# SixPotatoeV7.net
KiCad netlist of a schematic drawn in EAGLE
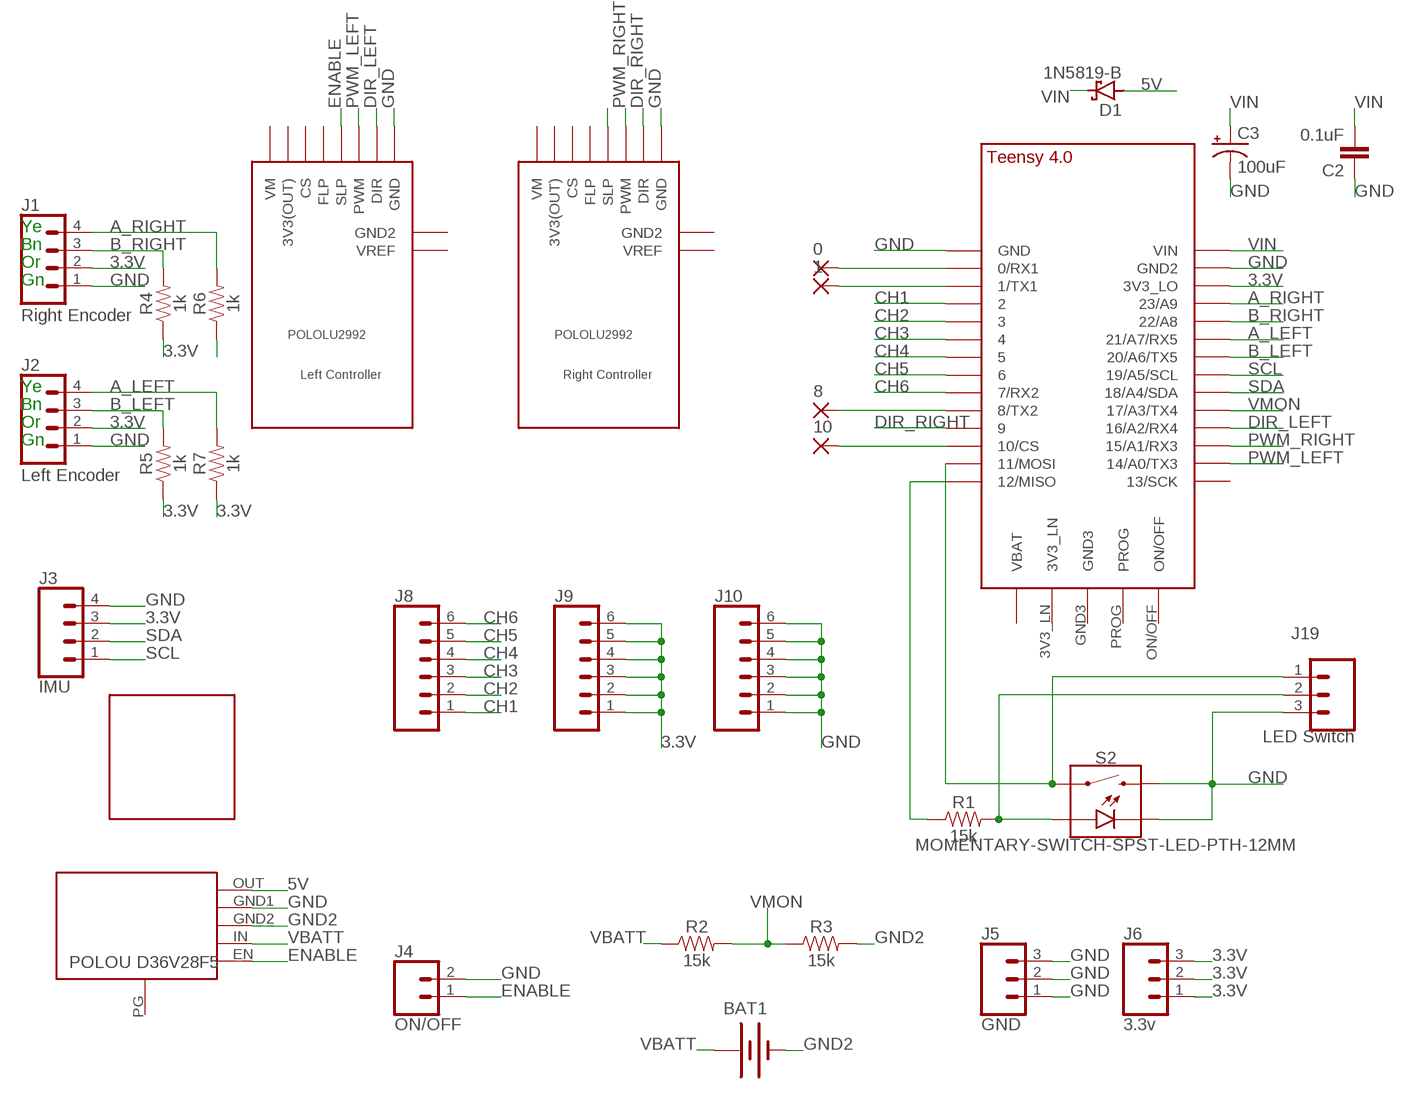
[diagram p0: schematic, sheet 1]

(export (version "E")
  (design (tool "Eeschema 10.0.6"))
  (components
    (comp (ref "0")
      (value "2,15/1,0")
      (footprint "eagle-import:2,15_1,0")
      (libsource (lib "eagle-import") (part "2,15/1,0"))
    )
    (comp (ref "1")
      (value "2,15/1,0")
      (footprint "eagle-import:2,15_1,0")
      (libsource (lib "eagle-import") (part "2,15/1,0"))
    )
    (comp (ref "8")
      (value "2,15/1,0")
      (footprint "eagle-import:2,15_1,0")
      (libsource (lib "eagle-import") (part "2,15/1,0"))
    )
    (comp (ref "10")
      (value "2,15/1,0")
      (footprint "eagle-import:2,15_1,0")
      (libsource (lib "eagle-import") (part "2,15/1,0"))
    )
    (comp (ref "BAT1")
      (value "XT60_MALE")
      (footprint "eagle-import:XT60")
      (libsource (lib "eagle-import") (part "XT60_MALE"))
    )
    (comp (ref "C2")
      (value "0.1uF")
      (footprint "eagle-import:CAP-PTH-SMALL-KIT")
      (libsource (lib "eagle-import") (part "0.1UF-KIT-EZ-50V-20%"))
    )
    (comp (ref "C3")
      (value "100uF")
      (footprint "eagle-import:CPOL-RADIAL-2.5MM-6.5MM")
      (libsource (lib "eagle-import") (part "100UF-POLAR-RADIAL-2.5MM-25V-20%"))
    )
    (comp (ref "D1")
      (value "1N5819-B")
      (footprint "eagle-import:DO41-7.6")
      (libsource (lib "eagle-import") (part "1N5819-B"))
    )
    (comp (ref "J1")
      (value "CONN_04")
      (footprint "eagle-import:1X04")
      (fields (field (name "ID") "Right Encoder"))
      (libsource (lib "eagle-import") (part "CONN_04"))
    )
    (comp (ref "J2")
      (value "CONN_04")
      (footprint "eagle-import:1X04")
      (fields (field (name "ID") "Left Encoder"))
      (libsource (lib "eagle-import") (part "CONN_04"))
    )
    (comp (ref "J3")
      (value "IMU")
      (footprint "eagle-import:1X04")
      (libsource (lib "eagle-import") (part "CONN_04"))
    )
    (comp (ref "J4")
      (value "ON/OFF")
      (footprint "eagle-import:1X02")
      (libsource (lib "eagle-import") (part "CONN_02"))
    )
    (comp (ref "J5")
      (value "GND")
      (footprint "eagle-import:1X03")
      (libsource (lib "eagle-import") (part "CONN_03"))
    )
    (comp (ref "J6")
      (value "3.3v")
      (footprint "eagle-import:1X03")
      (libsource (lib "eagle-import") (part "CONN_03"))
    )
    (comp (ref "J8")
      (value "CONN_06NO_SILK_FEMALE_PTH")
      (footprint "eagle-import:1X06_NO_SILK")
      (libsource (lib "eagle-import") (part "CONN_06NO_SILK_FEMALE_PTH"))
    )
    (comp (ref "J9")
      (value "CONN_06NO_SILK_FEMALE_PTH")
      (footprint "eagle-import:1X06_NO_SILK")
      (libsource (lib "eagle-import") (part "CONN_06NO_SILK_FEMALE_PTH"))
    )
    (comp (ref "J10")
      (value "CONN_06NO_SILK_FEMALE_PTH")
      (footprint "eagle-import:1X06_NO_SILK")
      (libsource (lib "eagle-import") (part "CONN_06NO_SILK_FEMALE_PTH"))
    )
    (comp (ref "J19")
      (value "CONN_03")
      (footprint "eagle-import:1X03")
      (fields (field (name "ID") "LED Switch"))
      (libsource (lib "eagle-import") (part "CONN_03"))
    )
    (comp (ref "R1")
      (value "15k")
      (footprint "eagle-import:AXIAL-0.3")
      (libsource (lib "eagle-import") (part "15KOHM-HORIZ-1/4W-5%"))
    )
    (comp (ref "R2")
      (value "15k")
      (footprint "eagle-import:AXIAL-0.3")
      (libsource (lib "eagle-import") (part "15KOHM-HORIZ-1/4W-5%"))
    )
    (comp (ref "R3")
      (value "15k")
      (footprint "eagle-import:AXIAL-0.3")
      (libsource (lib "eagle-import") (part "15KOHM-HORIZ-1/4W-5%"))
    )
    (comp (ref "R4")
      (value "1k")
      (footprint "eagle-import:AXIAL-0.3")
      (libsource (lib "eagle-import") (part "1KOHM-HORIZ-1/4W-1%"))
    )
    (comp (ref "R5")
      (value "1k")
      (footprint "eagle-import:AXIAL-0.3")
      (libsource (lib "eagle-import") (part "1KOHM-HORIZ-1/4W-1%"))
    )
    (comp (ref "R6")
      (value "1k")
      (footprint "eagle-import:AXIAL-0.3")
      (libsource (lib "eagle-import") (part "1KOHM-HORIZ-1/4W-1%"))
    )
    (comp (ref "R7")
      (value "1k")
      (footprint "eagle-import:AXIAL-0.3")
      (libsource (lib "eagle-import") (part "1KOHM-HORIZ-1/4W-1%"))
    )
    (comp (ref "S2")
      (value "MOMENTARY-SWITCH-SPST-LED-PTH-12MM")
      (footprint "eagle-import:TACTILE_SWITCH_LED_PTH_12MM")
      (libsource (lib "eagle-import") (part "MOMENTARY-SWITCH-SPST-LED-PTH-12MM"))
    )
    (comp (ref "U$1")
      (value "TEENSY_4.0")
      (footprint "eagle-import:TEENSY_4.0")
      (libsource (lib "eagle-import") (part "TEENSY_4.0"))
    )
    (comp (ref "U$2")
      (value "Left Controller")
      (footprint "eagle-import:POLOLU2992_2")
      (libsource (lib "eagle-import") (part "POLOLU2992_2"))
    )
    (comp (ref "U$3")
      (value "Right Controller")
      (footprint "eagle-import:POLOLU2992_2")
      (libsource (lib "eagle-import") (part "POLOLU2992_2"))
    )
    (comp (ref "U$4")
      (value "POLOU3782")
      (footprint "eagle-import:POLOU3782")
      (libsource (lib "eagle-import") (part "POLOU3782"))
    )
    (comp (ref "U$5")
      (value "SEN15335_NO_PTH")
      (footprint "eagle-import:SEN15335_NO_PTH")
      (libsource (lib "eagle-import") (part "SEN15335_NO_PTH"))
    )
  )
  (nets
    (net (code "1") (name "/3.3V") (class "Default")
      (node (ref "J1") (pin "2") (pinfunction "2_2") (pintype "passive"))
      (node (ref "J2") (pin "2") (pinfunction "2_2") (pintype "passive"))
      (node (ref "J3") (pin "3") (pinfunction "3_3") (pintype "passive"))
      (node (ref "J6") (pin "1") (pinfunction "1_1") (pintype "passive"))
      (node (ref "J6") (pin "2") (pinfunction "2_2") (pintype "passive"))
      (node (ref "J6") (pin "3") (pinfunction "3_3") (pintype "passive"))
      (node (ref "J9") (pin "1") (pinfunction "1_1") (pintype "passive"))
      (node (ref "J9") (pin "2") (pinfunction "2_2") (pintype "passive"))
      (node (ref "J9") (pin "3") (pinfunction "3_3") (pintype "passive"))
      (node (ref "J9") (pin "4") (pinfunction "4_4") (pintype "passive"))
      (node (ref "J9") (pin "5") (pinfunction "5_5") (pintype "passive"))
      (node (ref "J9") (pin "6") (pinfunction "6_6") (pintype "passive"))
      (node (ref "R4") (pin "P$1") (pinfunction "1_P$1") (pintype "passive"))
      (node (ref "R5") (pin "P$1") (pinfunction "1_P$1") (pintype "passive"))
      (node (ref "R6") (pin "P$1") (pinfunction "1_P$1") (pintype "passive"))
      (node (ref "R7") (pin "P$1") (pinfunction "1_P$1") (pintype "passive"))
      (node (ref "U$1") (pin "3V3_LO") (pinfunction "3V3_LO_3V3_LO") (pintype "bidirectional"))
    )
    (net (code "2") (name "/5V") (class "Default")
      (node (ref "D1") (pin "A") (pinfunction "A_A") (pintype "passive"))
      (node (ref "U$4") (pin "OUT") (pinfunction "OUT_OUT") (pintype "bidirectional"))
    )
    (net (code "3") (name "/A_LEFT") (class "Default")
      (node (ref "J2") (pin "4") (pinfunction "4_4") (pintype "passive"))
      (node (ref "R7") (pin "P$2") (pinfunction "2_P$2") (pintype "passive"))
      (node (ref "U$1") (pin "21/A7") (pinfunction "21/A7/RX5_21/A7") (pintype "bidirectional"))
    )
    (net (code "4") (name "/A_RIGHT") (class "Default")
      (node (ref "J1") (pin "4") (pinfunction "4_4") (pintype "passive"))
      (node (ref "R6") (pin "P$2") (pinfunction "2_P$2") (pintype "passive"))
      (node (ref "U$1") (pin "23/A9") (pinfunction "23/A9_23/A9") (pintype "bidirectional"))
    )
    (net (code "5") (name "/B_LEFT") (class "Default")
      (node (ref "J2") (pin "3") (pinfunction "3_3") (pintype "passive"))
      (node (ref "R5") (pin "P$2") (pinfunction "2_P$2") (pintype "passive"))
      (node (ref "U$1") (pin "20/A6") (pinfunction "20/A6/TX5_20/A6") (pintype "bidirectional"))
    )
    (net (code "6") (name "/B_RIGHT") (class "Default")
      (node (ref "J1") (pin "3") (pinfunction "3_3") (pintype "passive"))
      (node (ref "R4") (pin "P$2") (pinfunction "2_P$2") (pintype "passive"))
      (node (ref "U$1") (pin "22/A8") (pinfunction "22/A8_22/A8") (pintype "bidirectional"))
    )
    (net (code "7") (name "/CH1") (class "Default")
      (node (ref "J8") (pin "1") (pinfunction "1_1") (pintype "passive"))
      (node (ref "U$1") (pin "2") (pinfunction "2_2") (pintype "bidirectional"))
    )
    (net (code "8") (name "/CH2") (class "Default")
      (node (ref "J8") (pin "2") (pinfunction "2_2") (pintype "passive"))
      (node (ref "U$1") (pin "3/CANTX") (pinfunction "3_3/CANTX") (pintype "bidirectional"))
    )
    (net (code "9") (name "/CH3") (class "Default")
      (node (ref "J8") (pin "3") (pinfunction "3_3") (pintype "passive"))
      (node (ref "U$1") (pin "4/CANRX") (pinfunction "4_4/CANRX") (pintype "bidirectional"))
    )
    (net (code "10") (name "/CH4") (class "Default")
      (node (ref "J8") (pin "4") (pinfunction "4_4") (pintype "passive"))
      (node (ref "U$1") (pin "5") (pinfunction "5_5") (pintype "bidirectional"))
    )
    (net (code "11") (name "/CH5") (class "Default")
      (node (ref "J8") (pin "5") (pinfunction "5_5") (pintype "passive"))
      (node (ref "U$1") (pin "6") (pinfunction "6_6") (pintype "bidirectional"))
    )
    (net (code "12") (name "/CH6") (class "Default")
      (node (ref "J8") (pin "6") (pinfunction "6_6") (pintype "passive"))
      (node (ref "U$1") (pin "7") (pinfunction "7/RX2_7") (pintype "bidirectional"))
    )
    (net (code "13") (name "/DIR_LEFT") (class "Default")
      (node (ref "U$1") (pin "16/A2") (pinfunction "16/A2/RX4_16/A2") (pintype "bidirectional"))
      (node (ref "U$2") (pin "DIR") (pinfunction "DIR_DIR") (pintype "bidirectional"))
    )
    (net (code "14") (name "/DIR_RIGHT") (class "Default")
      (node (ref "U$1") (pin "9/CS") (pinfunction "9_9/CS") (pintype "bidirectional"))
      (node (ref "U$3") (pin "DIR") (pinfunction "DIR_DIR") (pintype "bidirectional"))
    )
    (net (code "15") (name "/ENABLE") (class "Default")
      (node (ref "J4") (pin "1") (pinfunction "1_1") (pintype "passive"))
      (node (ref "U$2") (pin "SLP") (pinfunction "SLP_SLP") (pintype "bidirectional"))
      (node (ref "U$3") (pin "SLP") (pinfunction "SLP_SLP") (pintype "bidirectional"))
      (node (ref "U$4") (pin "EN") (pinfunction "EN_EN") (pintype "bidirectional"))
    )
    (net (code "16") (name "/GND") (class "Default")
      (node (ref "C2") (pin "1") (pinfunction "1_1") (pintype "passive"))
      (node (ref "C3") (pin "2") (pinfunction "-_2") (pintype "passive"))
      (node (ref "J1") (pin "1") (pinfunction "1_1") (pintype "passive"))
      (node (ref "J10") (pin "1") (pinfunction "1_1") (pintype "passive"))
      (node (ref "J10") (pin "2") (pinfunction "2_2") (pintype "passive"))
      (node (ref "J10") (pin "3") (pinfunction "3_3") (pintype "passive"))
      (node (ref "J10") (pin "4") (pinfunction "4_4") (pintype "passive"))
      (node (ref "J10") (pin "5") (pinfunction "5_5") (pintype "passive"))
      (node (ref "J10") (pin "6") (pinfunction "6_6") (pintype "passive"))
      (node (ref "J19") (pin "3") (pinfunction "3_3") (pintype "passive"))
      (node (ref "J2") (pin "1") (pinfunction "1_1") (pintype "passive"))
      (node (ref "J3") (pin "4") (pinfunction "4_4") (pintype "passive"))
      (node (ref "J4") (pin "2") (pinfunction "2_2") (pintype "passive"))
      (node (ref "J5") (pin "1") (pinfunction "1_1") (pintype "passive"))
      (node (ref "J5") (pin "2") (pinfunction "2_2") (pintype "passive"))
      (node (ref "J5") (pin "3") (pinfunction "3_3") (pintype "passive"))
      (node (ref "S2") (pin "2") (pinfunction "2_2") (pintype "passive"))
      (node (ref "S2") (pin "C") (pinfunction "C_C") (pintype "passive"))
      (node (ref "U$1") (pin "GND") (pinfunction "GND_GND") (pintype "bidirectional"))
      (node (ref "U$1") (pin "GND2") (pinfunction "GND2_GND2") (pintype "bidirectional"))
      (node (ref "U$2") (pin "GND") (pinfunction "GND_GND") (pintype "bidirectional"))
      (node (ref "U$3") (pin "GND") (pinfunction "GND_GND") (pintype "bidirectional"))
      (node (ref "U$4") (pin "GND1") (pinfunction "GND1_GND1") (pintype "bidirectional"))
    )
    (net (code "17") (name "/GND2") (class "Default")
      (node (ref "BAT1") (pin "-") (pinfunction "-_-") (pintype "power_in"))
      (node (ref "R3") (pin "P$2") (pinfunction "2_P$2") (pintype "passive"))
      (node (ref "U$4") (pin "GND2") (pinfunction "GND2_GND2") (pintype "bidirectional"))
    )
    (net (code "18") (name "/PWM_LEFT") (class "Default")
      (node (ref "U$1") (pin "14/A0") (pinfunction "14/A0/TX3_14/A0") (pintype "bidirectional"))
      (node (ref "U$2") (pin "PWM") (pinfunction "PWM_PWM") (pintype "bidirectional"))
    )
    (net (code "19") (name "/PWM_RIGHT") (class "Default")
      (node (ref "U$1") (pin "15/A1") (pinfunction "15/A1/RX3_15/A1") (pintype "bidirectional"))
      (node (ref "U$3") (pin "PWM") (pinfunction "PWM_PWM") (pintype "bidirectional"))
    )
    (net (code "20") (name "/SCL") (class "Default")
      (node (ref "J3") (pin "1") (pinfunction "1_1") (pintype "passive"))
      (node (ref "U$1") (pin "19/A5/SCL") (pinfunction "19/A5/SCL_19/A5/SCL") (pintype "bidirectional"))
    )
    (net (code "21") (name "/SDA") (class "Default")
      (node (ref "J3") (pin "2") (pinfunction "2_2") (pintype "passive"))
      (node (ref "U$1") (pin "18/A4/SDA") (pinfunction "18/A4/SDA_18/A4/SDA") (pintype "bidirectional"))
    )
    (net (code "22") (name "/VBATT") (class "Default")
      (node (ref "BAT1") (pin "+") (pinfunction "+_+") (pintype "power_in"))
      (node (ref "R2") (pin "P$1") (pinfunction "1_P$1") (pintype "passive"))
      (node (ref "U$4") (pin "IN") (pinfunction "IN_IN") (pintype "bidirectional"))
    )
    (net (code "23") (name "/VIN") (class "Default")
      (node (ref "C2") (pin "2") (pinfunction "2_2") (pintype "passive"))
      (node (ref "C3") (pin "1") (pinfunction "+_1") (pintype "passive"))
      (node (ref "D1") (pin "C") (pinfunction "C_C") (pintype "passive"))
      (node (ref "U$1") (pin "VIN") (pinfunction "VIN_VIN") (pintype "bidirectional"))
    )
    (net (code "24") (name "/VMON") (class "Default")
      (node (ref "R2") (pin "P$2") (pinfunction "2_P$2") (pintype "passive"))
      (node (ref "R3") (pin "P$1") (pinfunction "1_P$1") (pintype "passive"))
      (node (ref "U$1") (pin "17/A3") (pinfunction "17/A3/TX4_17/A3") (pintype "bidirectional"))
    )
    (net (code "25") (name "Net-(0-P)") (class "Default")
      (node (ref "0") (pin "1") (pinfunction "P_1") (pintype "passive"))
      (node (ref "U$1") (pin "0/RX") (pinfunction "0/RX1_0/RX") (pintype "bidirectional"))
    )
    (net (code "26") (name "Net-(1-P)") (class "Default")
      (node (ref "1") (pin "1") (pinfunction "P_1") (pintype "passive"))
      (node (ref "U$1") (pin "1/TX") (pinfunction "1/TX1_1/TX") (pintype "bidirectional"))
    )
    (net (code "27") (name "Net-(8-P)") (class "Default")
      (node (ref "8") (pin "1") (pinfunction "P_1") (pintype "passive"))
      (node (ref "U$1") (pin "8") (pinfunction "8/TX2_8") (pintype "bidirectional"))
    )
    (net (code "28") (name "Net-(10-P)") (class "Default")
      (node (ref "10") (pin "1") (pinfunction "P_1") (pintype "passive"))
      (node (ref "U$1") (pin "10/CS") (pinfunction "10/CS_10/CS") (pintype "bidirectional"))
    )
    (net (code "29") (name "Net-(R1-1)") (class "Default")
      (node (ref "R1") (pin "P$1") (pinfunction "1_P$1") (pintype "passive"))
      (node (ref "U$1") (pin "12/MISO") (pinfunction "12/MISO_12/MISO") (pintype "bidirectional"))
    )
    (net (code "30") (name "Net-(R1-2)") (class "Default")
      (node (ref "J19") (pin "2") (pinfunction "2_2") (pintype "passive"))
      (node (ref "R1") (pin "P$2") (pinfunction "2_P$2") (pintype "passive"))
      (node (ref "S2") (pin "A") (pinfunction "A_A") (pintype "passive"))
    )
    (net (code "31") (name "Net-(S2-1)") (class "Default")
      (node (ref "J19") (pin "1") (pinfunction "1_1") (pintype "passive"))
      (node (ref "S2") (pin "4") (pinfunction "1_4") (pintype "passive"))
      (node (ref "U$1") (pin "11/MOSI") (pinfunction "11/MOSI_11/MOSI") (pintype "bidirectional"))
    )
    (net (code "32") (name "unconnected-(U$1-Pad3V3_LN)") (class "Default")
      (node (ref "U$1") (pin "3V3_LN") (pinfunction "3V3_LN_3V3_LN") (pintype "bidirectional"))
    )
    (net (code "33") (name "unconnected-(U$1-Pad13{slash}SCK)") (class "Default")
      (node (ref "U$1") (pin "13/SCK") (pinfunction "13/SCK_13/SCK") (pintype "bidirectional"))
    )
    (net (code "34") (name "unconnected-(U$1-PadGND3)") (class "Default")
      (node (ref "U$1") (pin "GND3") (pinfunction "GND3_GND3") (pintype "bidirectional"))
    )
    (net (code "35") (name "unconnected-(U$1-PadON{slash}OFF)") (class "Default")
      (node (ref "U$1") (pin "ON/OFF") (pinfunction "ON/OFF_ON/OFF") (pintype "bidirectional"))
    )
    (net (code "36") (name "unconnected-(U$1-PadPROG)") (class "Default")
      (node (ref "U$1") (pin "PROG") (pinfunction "PROG_PROG") (pintype "bidirectional"))
    )
    (net (code "37") (name "unconnected-(U$1-VBAT-PadVBAT\\)") (class "Default")
      (node (ref "U$1") (pin "VBAT\\") (pinfunction "VBAT_VBAT\\") (pintype "bidirectional"))
    )
    (net (code "38") (name "unconnected-(U$2-Pad3V3(OUT))") (class "Default")
      (node (ref "U$2") (pin "3V3(OUT)") (pinfunction "3V3(OUT)_3V3(OUT)") (pintype "bidirectional"))
    )
    (net (code "39") (name "unconnected-(U$2-PadCS)") (class "Default")
      (node (ref "U$2") (pin "CS") (pinfunction "CS_CS") (pintype "bidirectional"))
    )
    (net (code "40") (name "unconnected-(U$2-PadFLP)") (class "Default")
      (node (ref "U$2") (pin "FLP") (pinfunction "FLP_FLP") (pintype "bidirectional"))
    )
    (net (code "41") (name "unconnected-(U$2-PadGND2)") (class "Default")
      (node (ref "U$2") (pin "GND2") (pinfunction "GND2_GND2") (pintype "bidirectional"))
    )
    (net (code "42") (name "unconnected-(U$2-PadVM)") (class "Default")
      (node (ref "U$2") (pin "VM") (pinfunction "VM_VM") (pintype "bidirectional"))
    )
    (net (code "43") (name "unconnected-(U$2-PadVREF)") (class "Default")
      (node (ref "U$2") (pin "VREF") (pinfunction "VREF_VREF") (pintype "bidirectional"))
    )
    (net (code "44") (name "unconnected-(U$3-Pad3V3(OUT))") (class "Default")
      (node (ref "U$3") (pin "3V3(OUT)") (pinfunction "3V3(OUT)_3V3(OUT)") (pintype "bidirectional"))
    )
    (net (code "45") (name "unconnected-(U$3-PadCS)") (class "Default")
      (node (ref "U$3") (pin "CS") (pinfunction "CS_CS") (pintype "bidirectional"))
    )
    (net (code "46") (name "unconnected-(U$3-PadFLP)") (class "Default")
      (node (ref "U$3") (pin "FLP") (pinfunction "FLP_FLP") (pintype "bidirectional"))
    )
    (net (code "47") (name "unconnected-(U$3-PadGND2)") (class "Default")
      (node (ref "U$3") (pin "GND2") (pinfunction "GND2_GND2") (pintype "bidirectional"))
    )
    (net (code "48") (name "unconnected-(U$3-PadVM)") (class "Default")
      (node (ref "U$3") (pin "VM") (pinfunction "VM_VM") (pintype "bidirectional"))
    )
    (net (code "49") (name "unconnected-(U$3-PadVREF)") (class "Default")
      (node (ref "U$3") (pin "VREF") (pinfunction "VREF_VREF") (pintype "bidirectional"))
    )
    (net (code "50") (name "unconnected-(U$4-PadPG)") (class "Default")
      (node (ref "U$4") (pin "PG") (pinfunction "PG_PG") (pintype "bidirectional"))
    )
  )
)
